# ugly_fpga.net
KiCad netlist of a schematic drawn in EAGLE
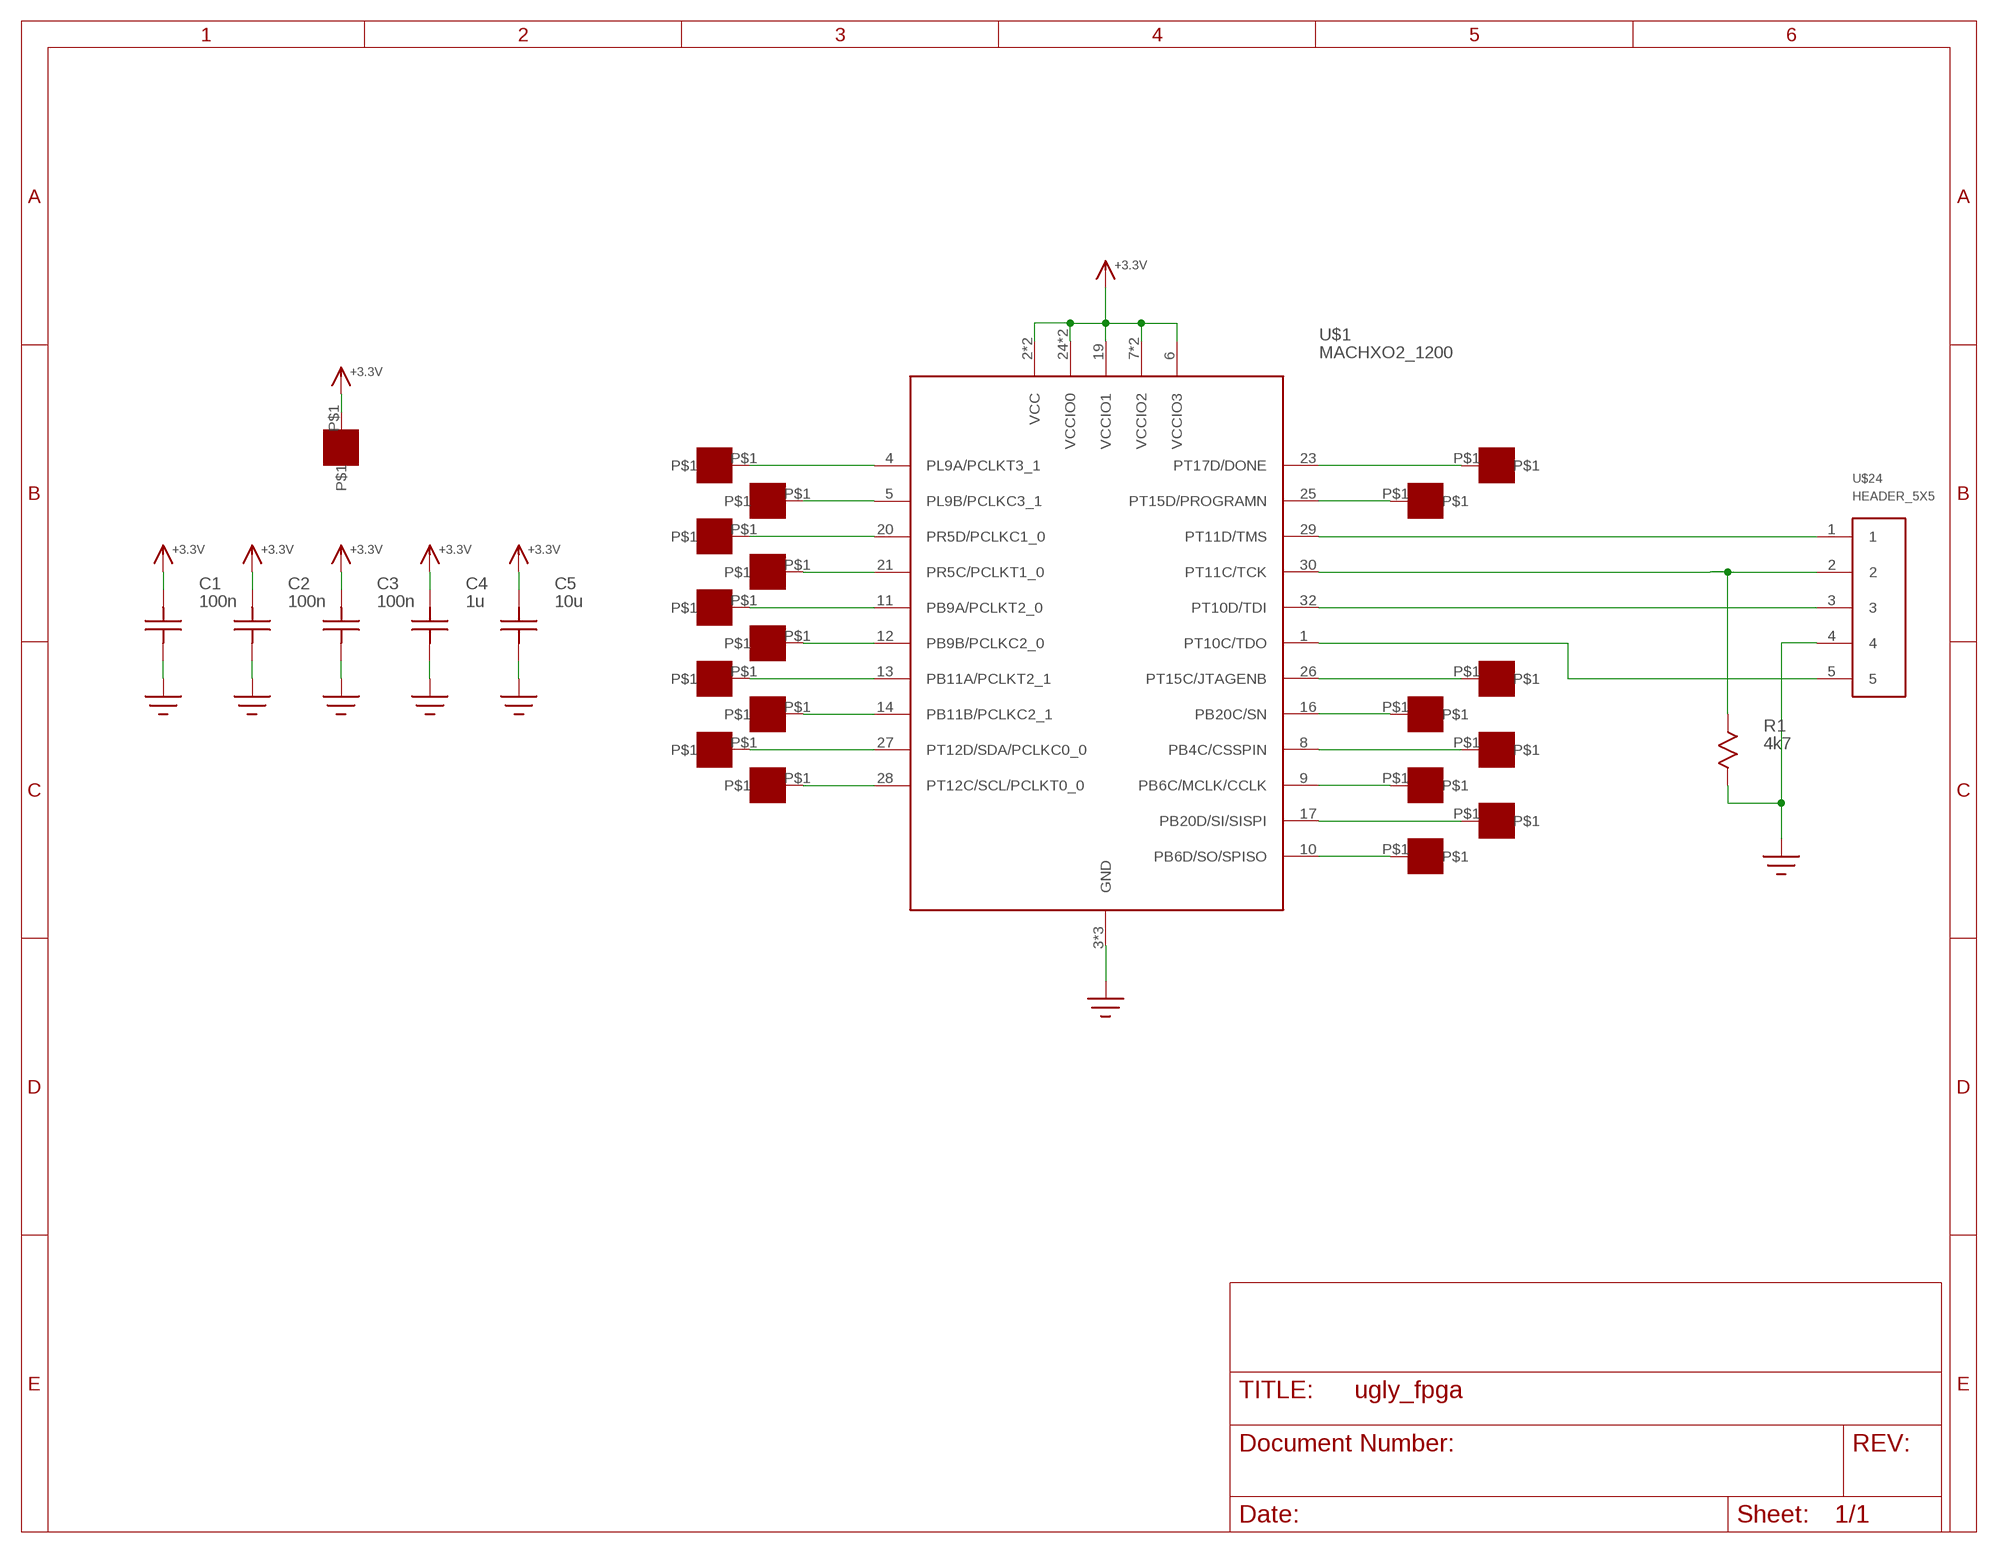
[diagram p0: schematic, sheet 1]

(export (version "E")
  (design (tool "Eeschema 10.0.6"))
  (components
    (comp (ref "C1")
      (value "100n")
      (footprint "eagle-import:C0603")
      (libsource (lib "eagle-import") (part "C0603"))
    )
    (comp (ref "C2")
      (value "100n")
      (footprint "eagle-import:C0603")
      (libsource (lib "eagle-import") (part "C0603"))
    )
    (comp (ref "C3")
      (value "100n")
      (footprint "eagle-import:C0603")
      (libsource (lib "eagle-import") (part "C0603"))
    )
    (comp (ref "C4")
      (value "1u")
      (footprint "eagle-import:C0603")
      (libsource (lib "eagle-import") (part "C0603"))
    )
    (comp (ref "C5")
      (value "10u")
      (footprint "eagle-import:C0603")
      (libsource (lib "eagle-import") (part "C0603"))
    )
    (comp (ref "R1")
      (value "4k7")
      (footprint "eagle-import:R0603")
      (libsource (lib "eagle-import") (part "R0603"))
    )
    (comp (ref "U$1")
      (value "MACHXO2_1200")
      (footprint "eagle-import:QFN32_5X5")
      (libsource (lib "eagle-import") (part "MACHXO2_1200"))
    )
    (comp (ref "U$6")
      (value "PAD50MIL")
      (footprint "eagle-import:PAD_50MIL")
      (libsource (lib "eagle-import") (part "PAD50MIL"))
    )
    (comp (ref "U$7")
      (value "PAD50MIL")
      (footprint "eagle-import:PAD_50MIL")
      (libsource (lib "eagle-import") (part "PAD50MIL"))
    )
    (comp (ref "U$8")
      (value "PAD50MIL")
      (footprint "eagle-import:PAD_50MIL")
      (libsource (lib "eagle-import") (part "PAD50MIL"))
    )
    (comp (ref "U$9")
      (value "PAD50MIL")
      (footprint "eagle-import:PAD_50MIL")
      (libsource (lib "eagle-import") (part "PAD50MIL"))
    )
    (comp (ref "U$10")
      (value "PAD50MIL")
      (footprint "eagle-import:PAD_50MIL")
      (libsource (lib "eagle-import") (part "PAD50MIL"))
    )
    (comp (ref "U$11")
      (value "PAD50MIL")
      (footprint "eagle-import:PAD_50MIL")
      (libsource (lib "eagle-import") (part "PAD50MIL"))
    )
    (comp (ref "U$12")
      (value "PAD50MIL")
      (footprint "eagle-import:PAD_50MIL")
      (libsource (lib "eagle-import") (part "PAD50MIL"))
    )
    (comp (ref "U$13")
      (value "PAD50MIL")
      (footprint "eagle-import:PAD_50MIL")
      (libsource (lib "eagle-import") (part "PAD50MIL"))
    )
    (comp (ref "U$14")
      (value "PAD50MIL")
      (footprint "eagle-import:PAD_50MIL")
      (libsource (lib "eagle-import") (part "PAD50MIL"))
    )
    (comp (ref "U$15")
      (value "PAD50MIL")
      (footprint "eagle-import:PAD_50MIL")
      (libsource (lib "eagle-import") (part "PAD50MIL"))
    )
    (comp (ref "U$16")
      (value "PAD50MIL")
      (footprint "eagle-import:PAD_50MIL")
      (libsource (lib "eagle-import") (part "PAD50MIL"))
    )
    (comp (ref "U$17")
      (value "PAD50MIL")
      (footprint "eagle-import:PAD_50MIL")
      (libsource (lib "eagle-import") (part "PAD50MIL"))
    )
    (comp (ref "U$18")
      (value "PAD50MIL")
      (footprint "eagle-import:PAD_50MIL")
      (libsource (lib "eagle-import") (part "PAD50MIL"))
    )
    (comp (ref "U$19")
      (value "PAD50MIL")
      (footprint "eagle-import:PAD_50MIL")
      (libsource (lib "eagle-import") (part "PAD50MIL"))
    )
    (comp (ref "U$20")
      (value "PAD50MIL")
      (footprint "eagle-import:PAD_50MIL")
      (libsource (lib "eagle-import") (part "PAD50MIL"))
    )
    (comp (ref "U$21")
      (value "PAD50MIL")
      (footprint "eagle-import:PAD_50MIL")
      (libsource (lib "eagle-import") (part "PAD50MIL"))
    )
    (comp (ref "U$22")
      (value "PAD50MIL")
      (footprint "eagle-import:PAD_50MIL")
      (libsource (lib "eagle-import") (part "PAD50MIL"))
    )
    (comp (ref "U$23")
      (value "PAD50MIL")
      (footprint "eagle-import:PAD_50MIL")
      (libsource (lib "eagle-import") (part "PAD50MIL"))
    )
    (comp (ref "U$24")
      (value "HEADER_5X5")
      (footprint "eagle-import:HEADER_SMT_1X5")
      (libsource (lib "eagle-import") (part "HEADER_5X5"))
    )
    (comp (ref "U$30")
      (value "PAD50MIL")
      (footprint "eagle-import:PAD_50MIL")
      (libsource (lib "eagle-import") (part "PAD50MIL"))
    )
  )
  (nets
    (net (code "1") (name "+3.3V") (class "Default")
      (node (ref "C1") (pin "P$2") (pinfunction "P$2_P$2") (pintype "bidirectional"))
      (node (ref "C2") (pin "P$2") (pinfunction "P$2_P$2") (pintype "bidirectional"))
      (node (ref "C3") (pin "P$2") (pinfunction "P$2_P$2") (pintype "bidirectional"))
      (node (ref "C4") (pin "P$2") (pinfunction "P$2_P$2") (pintype "bidirectional"))
      (node (ref "C5") (pin "P$2") (pinfunction "P$2_P$2") (pintype "bidirectional"))
      (node (ref "U$1") (pin "15") (pinfunction "VCCIO2_15") (pintype "bidirectional"))
      (node (ref "U$1") (pin "18") (pinfunction "VCC_18") (pintype "bidirectional"))
      (node (ref "U$1") (pin "19") (pinfunction "VCCIO1_19") (pintype "bidirectional"))
      (node (ref "U$1") (pin "2") (pinfunction "VCC_2") (pintype "bidirectional"))
      (node (ref "U$1") (pin "24") (pinfunction "VCCIO0_24") (pintype "bidirectional"))
      (node (ref "U$1") (pin "31") (pinfunction "VCCIO0_31") (pintype "bidirectional"))
      (node (ref "U$1") (pin "6") (pinfunction "VCCIO3_6") (pintype "bidirectional"))
      (node (ref "U$1") (pin "7") (pinfunction "VCCIO2_7") (pintype "bidirectional"))
      (node (ref "U$30") (pin "P$1") (pinfunction "P$1_P$1") (pintype "bidirectional"))
    )
    (net (code "2") (name "GND") (class "Default")
      (node (ref "C1") (pin "P$1") (pinfunction "P$1_P$1") (pintype "bidirectional"))
      (node (ref "C2") (pin "P$1") (pinfunction "P$1_P$1") (pintype "bidirectional"))
      (node (ref "C3") (pin "P$1") (pinfunction "P$1_P$1") (pintype "bidirectional"))
      (node (ref "C4") (pin "P$1") (pinfunction "P$1_P$1") (pintype "bidirectional"))
      (node (ref "C5") (pin "P$1") (pinfunction "P$1_P$1") (pintype "bidirectional"))
      (node (ref "R1") (pin "P$2") (pinfunction "P$4_P$2") (pintype "bidirectional"))
      (node (ref "U$1") (pin "22") (pinfunction "GND_22") (pintype "bidirectional"))
      (node (ref "U$1") (pin "3") (pinfunction "GND_3") (pintype "bidirectional"))
      (node (ref "U$1") (pin "PAD") (pinfunction "GND_PAD") (pintype "bidirectional"))
      (node (ref "U$24") (pin "4") (pinfunction "4_4") (pintype "bidirectional"))
    )
    (net (code "3") (name "Net-(R1-P$3)") (class "Default")
      (node (ref "R1") (pin "P$1") (pinfunction "P$3_P$1") (pintype "bidirectional"))
      (node (ref "U$1") (pin "30") (pinfunction "PT11C/TCK_30") (pintype "bidirectional"))
      (node (ref "U$24") (pin "2") (pinfunction "2_2") (pintype "bidirectional"))
    )
    (net (code "4") (name "Net-(U$1-PB4C{slash}CSSPIN)") (class "Default")
      (node (ref "U$1") (pin "8") (pinfunction "PB4C/CSSPIN_8") (pintype "bidirectional"))
      (node (ref "U$19") (pin "P$1") (pinfunction "P$1_P$1") (pintype "bidirectional"))
    )
    (net (code "5") (name "Net-(U$1-PB6C{slash}MCLK{slash}CCLK)") (class "Default")
      (node (ref "U$1") (pin "9") (pinfunction "PB6C/MCLK/CCLK_9") (pintype "bidirectional"))
      (node (ref "U$18") (pin "P$1") (pinfunction "P$1_P$1") (pintype "bidirectional"))
    )
    (net (code "6") (name "Net-(U$1-PB6D{slash}SO{slash}SPISO)") (class "Default")
      (node (ref "U$1") (pin "10") (pinfunction "PB6D/SO/SPISO_10") (pintype "bidirectional"))
      (node (ref "U$16") (pin "P$1") (pinfunction "P$1_P$1") (pintype "bidirectional"))
    )
    (net (code "7") (name "Net-(U$1-PB9A{slash}PCLKT2_0)") (class "Default")
      (node (ref "U$1") (pin "11") (pinfunction "PB9A/PCLKT2_0_11") (pintype "bidirectional"))
      (node (ref "U$10") (pin "P$1") (pinfunction "P$1_P$1") (pintype "bidirectional"))
    )
    (net (code "8") (name "Net-(U$1-PB9B{slash}PCLKC2_0)") (class "Default")
      (node (ref "U$1") (pin "12") (pinfunction "PB9B/PCLKC2_0_12") (pintype "bidirectional"))
      (node (ref "U$11") (pin "P$1") (pinfunction "P$1_P$1") (pintype "bidirectional"))
    )
    (net (code "9") (name "Net-(U$1-PB11A{slash}PCLKT2_1)") (class "Default")
      (node (ref "U$1") (pin "13") (pinfunction "PB11A/PCLKT2_1_13") (pintype "bidirectional"))
      (node (ref "U$12") (pin "P$1") (pinfunction "P$1_P$1") (pintype "bidirectional"))
    )
    (net (code "10") (name "Net-(U$1-PB11B{slash}PCLKC2_1)") (class "Default")
      (node (ref "U$1") (pin "14") (pinfunction "PB11B/PCLKC2_1_14") (pintype "bidirectional"))
      (node (ref "U$13") (pin "P$1") (pinfunction "P$1_P$1") (pintype "bidirectional"))
    )
    (net (code "11") (name "Net-(U$1-PB20C{slash}SN)") (class "Default")
      (node (ref "U$1") (pin "16") (pinfunction "PB20C/SN_16") (pintype "bidirectional"))
      (node (ref "U$20") (pin "P$1") (pinfunction "P$1_P$1") (pintype "bidirectional"))
    )
    (net (code "12") (name "Net-(U$1-PB20D{slash}SI{slash}SISPI)") (class "Default")
      (node (ref "U$1") (pin "17") (pinfunction "PB20D/SI/SISPI_17") (pintype "bidirectional"))
      (node (ref "U$17") (pin "P$1") (pinfunction "P$1_P$1") (pintype "bidirectional"))
    )
    (net (code "13") (name "Net-(U$1-PL9A{slash}PCLKT3_1)") (class "Default")
      (node (ref "U$1") (pin "4") (pinfunction "PL9A/PCLKT3_1_4") (pintype "bidirectional"))
      (node (ref "U$6") (pin "P$1") (pinfunction "P$1_P$1") (pintype "bidirectional"))
    )
    (net (code "14") (name "Net-(U$1-PL9B{slash}PCLKC3_1)") (class "Default")
      (node (ref "U$1") (pin "5") (pinfunction "PL9B/PCLKC3_1_5") (pintype "bidirectional"))
      (node (ref "U$7") (pin "P$1") (pinfunction "P$1_P$1") (pintype "bidirectional"))
    )
    (net (code "15") (name "Net-(U$1-PR5C{slash}PCLKT1_0)") (class "Default")
      (node (ref "U$1") (pin "21") (pinfunction "PR5C/PCLKT1_0_21") (pintype "bidirectional"))
      (node (ref "U$9") (pin "P$1") (pinfunction "P$1_P$1") (pintype "bidirectional"))
    )
    (net (code "16") (name "Net-(U$1-PR5D{slash}PCLKC1_0)") (class "Default")
      (node (ref "U$1") (pin "20") (pinfunction "PR5D/PCLKC1_0_20") (pintype "bidirectional"))
      (node (ref "U$8") (pin "P$1") (pinfunction "P$1_P$1") (pintype "bidirectional"))
    )
    (net (code "17") (name "Net-(U$1-PT10C{slash}TDO)") (class "Default")
      (node (ref "U$1") (pin "1") (pinfunction "PT10C/TDO_1") (pintype "bidirectional"))
      (node (ref "U$24") (pin "5") (pinfunction "5_5") (pintype "bidirectional"))
    )
    (net (code "18") (name "Net-(U$1-PT10D{slash}TDI)") (class "Default")
      (node (ref "U$1") (pin "32") (pinfunction "PT10D/TDI_32") (pintype "bidirectional"))
      (node (ref "U$24") (pin "3") (pinfunction "3_3") (pintype "bidirectional"))
    )
    (net (code "19") (name "Net-(U$1-PT11D{slash}TMS)") (class "Default")
      (node (ref "U$1") (pin "29") (pinfunction "PT11D/TMS_29") (pintype "bidirectional"))
      (node (ref "U$24") (pin "1") (pinfunction "1_1") (pintype "bidirectional"))
    )
    (net (code "20") (name "Net-(U$1-PT12C{slash}SCL{slash}PCLKT0_0)") (class "Default")
      (node (ref "U$1") (pin "28") (pinfunction "PT12C/SCL/PCLKT0_0_28") (pintype "bidirectional"))
      (node (ref "U$15") (pin "P$1") (pinfunction "P$1_P$1") (pintype "bidirectional"))
    )
    (net (code "21") (name "Net-(U$1-PT12D{slash}SDA{slash}PCLKC0_0)") (class "Default")
      (node (ref "U$1") (pin "27") (pinfunction "PT12D/SDA/PCLKC0_0_27") (pintype "bidirectional"))
      (node (ref "U$14") (pin "P$1") (pinfunction "P$1_P$1") (pintype "bidirectional"))
    )
    (net (code "22") (name "Net-(U$1-PT15C{slash}JTAGENB)") (class "Default")
      (node (ref "U$1") (pin "26") (pinfunction "PT15C/JTAGENB_26") (pintype "bidirectional"))
      (node (ref "U$21") (pin "P$1") (pinfunction "P$1_P$1") (pintype "bidirectional"))
    )
    (net (code "23") (name "Net-(U$1-PT15D{slash}PROGRAMN)") (class "Default")
      (node (ref "U$1") (pin "25") (pinfunction "PT15D/PROGRAMN_25") (pintype "bidirectional"))
      (node (ref "U$23") (pin "P$1") (pinfunction "P$1_P$1") (pintype "bidirectional"))
    )
    (net (code "24") (name "Net-(U$1-PT17D{slash}DONE)") (class "Default")
      (node (ref "U$1") (pin "23") (pinfunction "PT17D/DONE_23") (pintype "bidirectional"))
      (node (ref "U$22") (pin "P$1") (pinfunction "P$1_P$1") (pintype "bidirectional"))
    )
  )
)
